# Business_Card.net
KiCad netlist of a schematic drawn in EAGLE
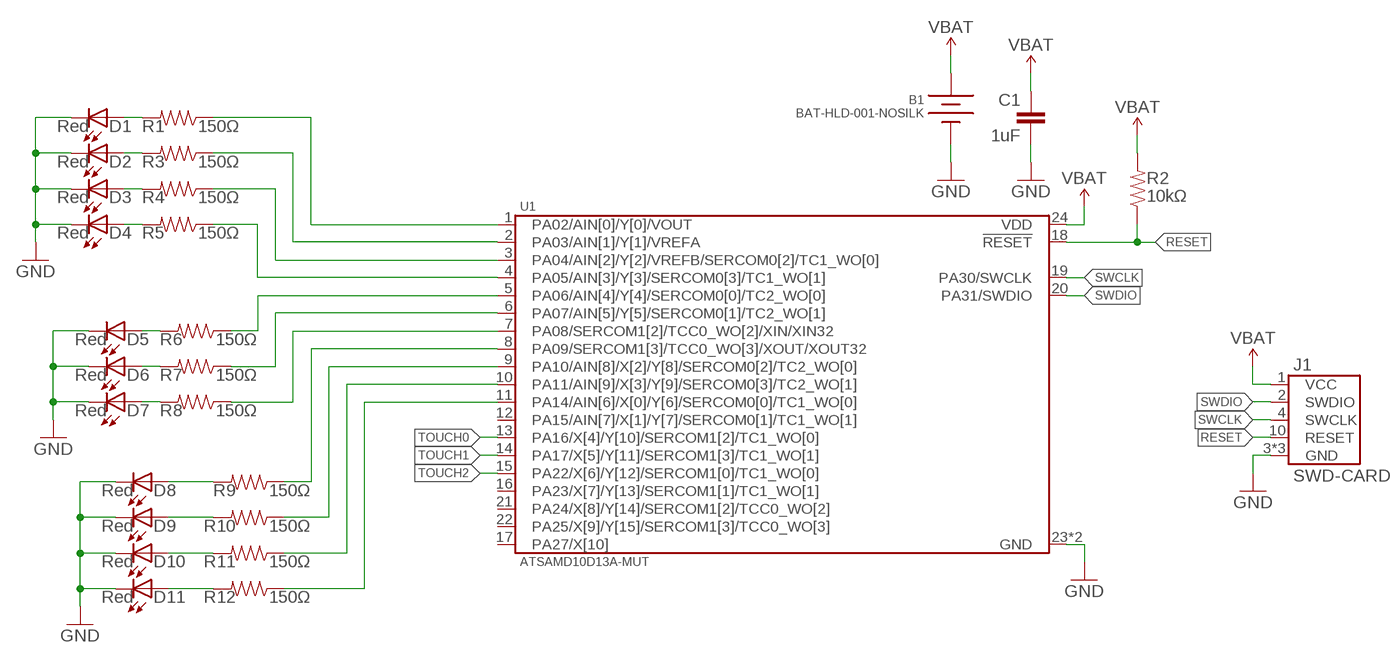
[diagram p0: schematic, sheet 1]

(export (version "E")
  (design (tool "Eeschema 10.0.6"))
  (components
    (comp (ref "B1")
      (value "BAT-HLD-001-NOSILK")
      (footprint "eagle-import:BK-912-G-TR")
      (libsource (lib "eagle-import") (part "BAT-HLD-001-NOSILK"))
    )
    (comp (ref "C1")
      (value "1uF")
      (footprint "eagle-import:0603-CAP")
      (libsource (lib "eagle-import") (part "CAP-0603"))
    )
    (comp (ref "D1")
      (value "Red")
      (footprint "eagle-import:0805-LED")
      (libsource (lib "eagle-import") (part "LED-0805"))
    )
    (comp (ref "D2")
      (value "Red")
      (footprint "eagle-import:0805-LED")
      (libsource (lib "eagle-import") (part "LED-0805"))
    )
    (comp (ref "D3")
      (value "Red")
      (footprint "eagle-import:0805-LED")
      (libsource (lib "eagle-import") (part "LED-0805"))
    )
    (comp (ref "D4")
      (value "Red")
      (footprint "eagle-import:0805-LED")
      (libsource (lib "eagle-import") (part "LED-0805"))
    )
    (comp (ref "D5")
      (value "Red")
      (footprint "eagle-import:0805-LED")
      (libsource (lib "eagle-import") (part "LED-0805"))
    )
    (comp (ref "D6")
      (value "Red")
      (footprint "eagle-import:0805-LED")
      (libsource (lib "eagle-import") (part "LED-0805"))
    )
    (comp (ref "D7")
      (value "Red")
      (footprint "eagle-import:0805-LED")
      (libsource (lib "eagle-import") (part "LED-0805"))
    )
    (comp (ref "D8")
      (value "Red")
      (footprint "eagle-import:0805-LED")
      (libsource (lib "eagle-import") (part "LED-0805"))
    )
    (comp (ref "D9")
      (value "Red")
      (footprint "eagle-import:0805-LED")
      (libsource (lib "eagle-import") (part "LED-0805"))
    )
    (comp (ref "D10")
      (value "Red")
      (footprint "eagle-import:0805-LED")
      (libsource (lib "eagle-import") (part "LED-0805"))
    )
    (comp (ref "D11")
      (value "Red")
      (footprint "eagle-import:0805-LED")
      (libsource (lib "eagle-import") (part "LED-0805"))
    )
    (comp (ref "J1")
      (value "SWD-CARD")
      (footprint "eagle-import:CWR-170-10-0203")
      (libsource (lib "eagle-import") (part "SWD-CARD"))
    )
    (comp (ref "R1")
      (value "150Ω")
      (footprint "eagle-import:0603-CAP")
      (libsource (lib "eagle-import") (part "RESISTOR-0603"))
    )
    (comp (ref "R2")
      (value "10kΩ")
      (footprint "eagle-import:0603-CAP")
      (libsource (lib "eagle-import") (part "RESISTOR-0603"))
    )
    (comp (ref "R3")
      (value "150Ω")
      (footprint "eagle-import:0603-CAP")
      (libsource (lib "eagle-import") (part "RESISTOR-0603"))
    )
    (comp (ref "R4")
      (value "150Ω")
      (footprint "eagle-import:0603-CAP")
      (libsource (lib "eagle-import") (part "RESISTOR-0603"))
    )
    (comp (ref "R5")
      (value "150Ω")
      (footprint "eagle-import:0603-CAP")
      (libsource (lib "eagle-import") (part "RESISTOR-0603"))
    )
    (comp (ref "R6")
      (value "150Ω")
      (footprint "eagle-import:0603-CAP")
      (libsource (lib "eagle-import") (part "RESISTOR-0603"))
    )
    (comp (ref "R7")
      (value "150Ω")
      (footprint "eagle-import:0603-CAP")
      (libsource (lib "eagle-import") (part "RESISTOR-0603"))
    )
    (comp (ref "R8")
      (value "150Ω")
      (footprint "eagle-import:0603-CAP")
      (libsource (lib "eagle-import") (part "RESISTOR-0603"))
    )
    (comp (ref "R9")
      (value "150Ω")
      (footprint "eagle-import:0603-CAP")
      (libsource (lib "eagle-import") (part "RESISTOR-0603"))
    )
    (comp (ref "R10")
      (value "150Ω")
      (footprint "eagle-import:0603-CAP")
      (libsource (lib "eagle-import") (part "RESISTOR-0603"))
    )
    (comp (ref "R11")
      (value "150Ω")
      (footprint "eagle-import:0603-CAP")
      (libsource (lib "eagle-import") (part "RESISTOR-0603"))
    )
    (comp (ref "R12")
      (value "150Ω")
      (footprint "eagle-import:0603-CAP")
      (libsource (lib "eagle-import") (part "RESISTOR-0603"))
    )
    (comp (ref "U1")
      (value "ATSAMD10D13A-MUT")
      (footprint "eagle-import:QFN-24")
      (libsource (lib "eagle-import") (part "ATSAMD10D13A-MUT"))
    )
  )
  (nets
    (net (code "1") (name "GND") (class "Default")
      (node (ref "B1") (pin "-") (pinfunction "N_-") (pintype "bidirectional"))
      (node (ref "C1") (pin "2") (pinfunction "2_2") (pintype "passive"))
      (node (ref "D1") (pin "C") (pinfunction "C_C") (pintype "passive"))
      (node (ref "D10") (pin "C") (pinfunction "C_C") (pintype "passive"))
      (node (ref "D11") (pin "C") (pinfunction "C_C") (pintype "passive"))
      (node (ref "D2") (pin "C") (pinfunction "C_C") (pintype "passive"))
      (node (ref "D3") (pin "C") (pinfunction "C_C") (pintype "passive"))
      (node (ref "D4") (pin "C") (pinfunction "C_C") (pintype "passive"))
      (node (ref "D5") (pin "C") (pinfunction "C_C") (pintype "passive"))
      (node (ref "D6") (pin "C") (pinfunction "C_C") (pintype "passive"))
      (node (ref "D7") (pin "C") (pinfunction "C_C") (pintype "passive"))
      (node (ref "D8") (pin "C") (pinfunction "C_C") (pintype "passive"))
      (node (ref "D9") (pin "C") (pinfunction "C_C") (pintype "passive"))
      (node (ref "J1") (pin "3") (pinfunction "GND_3") (pintype "bidirectional"))
      (node (ref "J1") (pin "5") (pinfunction "GND_5") (pintype "bidirectional"))
      (node (ref "J1") (pin "9") (pinfunction "GND_9") (pintype "bidirectional"))
      (node (ref "U1") (pin "23") (pinfunction "GND_23") (pintype "bidirectional"))
      (node (ref "U1") (pin "P$1") (pinfunction "GND_P$1") (pintype "bidirectional"))
    )
    (net (code "2") (name "Net-(D1-PadA)") (class "Default")
      (node (ref "D1") (pin "A") (pinfunction "A_A") (pintype "passive"))
      (node (ref "R1") (pin "2") (pinfunction "2_2") (pintype "passive"))
    )
    (net (code "3") (name "Net-(D2-PadA)") (class "Default")
      (node (ref "D2") (pin "A") (pinfunction "A_A") (pintype "passive"))
      (node (ref "R3") (pin "2") (pinfunction "2_2") (pintype "passive"))
    )
    (net (code "4") (name "Net-(D3-PadA)") (class "Default")
      (node (ref "D3") (pin "A") (pinfunction "A_A") (pintype "passive"))
      (node (ref "R4") (pin "2") (pinfunction "2_2") (pintype "passive"))
    )
    (net (code "5") (name "Net-(D4-PadA)") (class "Default")
      (node (ref "D4") (pin "A") (pinfunction "A_A") (pintype "passive"))
      (node (ref "R5") (pin "2") (pinfunction "2_2") (pintype "passive"))
    )
    (net (code "6") (name "Net-(D5-PadA)") (class "Default")
      (node (ref "D5") (pin "A") (pinfunction "A_A") (pintype "passive"))
      (node (ref "R6") (pin "2") (pinfunction "2_2") (pintype "passive"))
    )
    (net (code "7") (name "Net-(D6-PadA)") (class "Default")
      (node (ref "D6") (pin "A") (pinfunction "A_A") (pintype "passive"))
      (node (ref "R7") (pin "2") (pinfunction "2_2") (pintype "passive"))
    )
    (net (code "8") (name "Net-(D7-PadA)") (class "Default")
      (node (ref "D7") (pin "A") (pinfunction "A_A") (pintype "passive"))
      (node (ref "R8") (pin "2") (pinfunction "2_2") (pintype "passive"))
    )
    (net (code "9") (name "Net-(D8-PadA)") (class "Default")
      (node (ref "D8") (pin "A") (pinfunction "A_A") (pintype "passive"))
      (node (ref "R9") (pin "2") (pinfunction "2_2") (pintype "passive"))
    )
    (net (code "10") (name "Net-(D9-PadA)") (class "Default")
      (node (ref "D9") (pin "A") (pinfunction "A_A") (pintype "passive"))
      (node (ref "R10") (pin "2") (pinfunction "2_2") (pintype "passive"))
    )
    (net (code "11") (name "Net-(D10-PadA)") (class "Default")
      (node (ref "D10") (pin "A") (pinfunction "A_A") (pintype "passive"))
      (node (ref "R11") (pin "2") (pinfunction "2_2") (pintype "passive"))
    )
    (net (code "12") (name "Net-(D11-PadA)") (class "Default")
      (node (ref "D11") (pin "A") (pinfunction "A_A") (pintype "passive"))
      (node (ref "R12") (pin "2") (pinfunction "2_2") (pintype "passive"))
    )
    (net (code "13") (name "Net-(U1-PA02{slash}AIN[0]{slash}Y[0]{slash}VOUT)") (class "Default")
      (node (ref "R1") (pin "1") (pinfunction "1_1") (pintype "passive"))
      (node (ref "U1") (pin "1") (pinfunction "PA02/AIN[0]/Y[0]/VOUT_1") (pintype "bidirectional"))
    )
    (net (code "14") (name "Net-(U1-PA03{slash}AIN[1]{slash}Y[1]{slash}VREFA)") (class "Default")
      (node (ref "R3") (pin "1") (pinfunction "1_1") (pintype "passive"))
      (node (ref "U1") (pin "2") (pinfunction "PA03/AIN[1]/Y[1]/VREFA_2") (pintype "bidirectional"))
    )
    (net (code "15") (name "Net-(U1-PA04{slash}AIN[2]{slash}Y[2]{slash}VREFB{slash}SERCOM0[2]{slash}TC1_WO[0])") (class "Default")
      (node (ref "R4") (pin "1") (pinfunction "1_1") (pintype "passive"))
      (node (ref "U1") (pin "3") (pinfunction "PA04/AIN[2]/Y[2]/VREFB/SERCOM0[2]/TC1_WO[0]_3") (pintype "bidirectional"))
    )
    (net (code "16") (name "Net-(U1-PA05{slash}AIN[3]{slash}Y[3]{slash}SERCOM0[3]{slash}TC1_WO[1])") (class "Default")
      (node (ref "R5") (pin "1") (pinfunction "1_1") (pintype "passive"))
      (node (ref "U1") (pin "4") (pinfunction "PA05/AIN[3]/Y[3]/SERCOM0[3]/TC1_WO[1]_4") (pintype "bidirectional"))
    )
    (net (code "17") (name "Net-(U1-PA06{slash}AIN[4]{slash}Y[4]{slash}SERCOM0[0]{slash}TC2_WO[0])") (class "Default")
      (node (ref "R6") (pin "1") (pinfunction "1_1") (pintype "passive"))
      (node (ref "U1") (pin "5") (pinfunction "PA06/AIN[4]/Y[4]/SERCOM0[0]/TC2_WO[0]_5") (pintype "bidirectional"))
    )
    (net (code "18") (name "Net-(U1-PA07{slash}AIN[5]{slash}Y[5]{slash}SERCOM0[1]{slash}TC2_WO[1])") (class "Default")
      (node (ref "R7") (pin "1") (pinfunction "1_1") (pintype "passive"))
      (node (ref "U1") (pin "6") (pinfunction "PA07/AIN[5]/Y[5]/SERCOM0[1]/TC2_WO[1]_6") (pintype "bidirectional"))
    )
    (net (code "19") (name "Net-(U1-PA08{slash}SERCOM1[2]{slash}TCC0_WO[2]{slash}XIN{slash}XIN32)") (class "Default")
      (node (ref "R8") (pin "1") (pinfunction "1_1") (pintype "passive"))
      (node (ref "U1") (pin "7") (pinfunction "PA08/SERCOM1[2]/TCC0_WO[2]/XIN/XIN32_7") (pintype "bidirectional"))
    )
    (net (code "20") (name "Net-(U1-PA09{slash}SERCOM1[3]{slash}TCC0_WO[3]{slash}XOUT{slash}XOUT32)") (class "Default")
      (node (ref "R9") (pin "1") (pinfunction "1_1") (pintype "passive"))
      (node (ref "U1") (pin "8") (pinfunction "PA09/SERCOM1[3]/TCC0_WO[3]/XOUT/XOUT32_8") (pintype "bidirectional"))
    )
    (net (code "21") (name "Net-(U1-PA10{slash}AIN[8]{slash}X[2]{slash}Y[8]{slash}SERCOM0[2]{slash}TC2_WO[0])") (class "Default")
      (node (ref "R10") (pin "1") (pinfunction "1_1") (pintype "passive"))
      (node (ref "U1") (pin "9") (pinfunction "PA10/AIN[8]/X[2]/Y[8]/SERCOM0[2]/TC2_WO[0]_9") (pintype "bidirectional"))
    )
    (net (code "22") (name "Net-(U1-PA11{slash}AIN[9]{slash}X[3]{slash}Y[9]{slash}SERCOM0[3]{slash}TC2_WO[1])") (class "Default")
      (node (ref "R11") (pin "1") (pinfunction "1_1") (pintype "passive"))
      (node (ref "U1") (pin "10") (pinfunction "PA11/AIN[9]/X[3]/Y[9]/SERCOM0[3]/TC2_WO[1]_10") (pintype "bidirectional"))
    )
    (net (code "23") (name "Net-(U1-PA14{slash}AIN[6]{slash}X[0]{slash}Y[6]{slash}SERCOM0[0]{slash}TC1_WO[0])") (class "Default")
      (node (ref "R12") (pin "1") (pinfunction "1_1") (pintype "passive"))
      (node (ref "U1") (pin "11") (pinfunction "PA14/AIN[6]/X[0]/Y[6]/SERCOM0[0]/TC1_WO[0]_11") (pintype "bidirectional"))
    )
    (net (code "24") (name "RESET") (class "Default")
      (node (ref "J1") (pin "10") (pinfunction "RESET_10") (pintype "bidirectional"))
      (node (ref "R2") (pin "1") (pinfunction "1_1") (pintype "passive"))
      (node (ref "U1") (pin "18") (pinfunction "~{RESET}_18") (pintype "bidirectional"))
    )
    (net (code "25") (name "SWCLK") (class "Default")
      (node (ref "J1") (pin "4") (pinfunction "SWCLK_4") (pintype "bidirectional"))
      (node (ref "U1") (pin "19") (pinfunction "PA30/SWCLK_19") (pintype "bidirectional"))
    )
    (net (code "26") (name "SWDIO") (class "Default")
      (node (ref "J1") (pin "2") (pinfunction "SWDIO_2") (pintype "bidirectional"))
      (node (ref "U1") (pin "20") (pinfunction "PA31/SWDIO_20") (pintype "bidirectional"))
    )
    (net (code "27") (name "TOUCH0") (class "Default")
      (node (ref "U1") (pin "13") (pinfunction "PA16/X[4]/Y[10]/SERCOM1[2]/TC1_WO[0]_13") (pintype "bidirectional"))
    )
    (net (code "28") (name "TOUCH1") (class "Default")
      (node (ref "U1") (pin "14") (pinfunction "PA17/X[5]/Y[11]/SERCOM1[3]/TC1_WO[1]_14") (pintype "bidirectional"))
    )
    (net (code "29") (name "TOUCH2") (class "Default")
      (node (ref "U1") (pin "15") (pinfunction "PA22/X[6]/Y[12]/SERCOM1[0]/TC1_WO[0]_15") (pintype "bidirectional"))
    )
    (net (code "30") (name "VBAT") (class "Default")
      (node (ref "B1") (pin "+1") (pinfunction "P_+1") (pintype "bidirectional"))
      (node (ref "B1") (pin "+2") (pinfunction "P_+2") (pintype "bidirectional"))
      (node (ref "C1") (pin "1") (pinfunction "1_1") (pintype "passive"))
      (node (ref "J1") (pin "1") (pinfunction "VCC_1") (pintype "bidirectional"))
      (node (ref "R2") (pin "2") (pinfunction "2_2") (pintype "passive"))
      (node (ref "U1") (pin "24") (pinfunction "VDD_24") (pintype "bidirectional"))
    )
    (net (code "31") (name "unconnected-(U1-PA15{slash}AIN[7]{slash}X[1]{slash}Y[7]{slash}SERCOM0[1]{slash}TC1_WO[1]-Pad12)") (class "Default")
      (node (ref "U1") (pin "12") (pinfunction "PA15/AIN[7]/X[1]/Y[7]/SERCOM0[1]/TC1_WO[1]_12") (pintype "bidirectional"))
    )
    (net (code "32") (name "unconnected-(U1-PA23{slash}X[7]{slash}Y[13]{slash}SERCOM1[1]{slash}TC1_WO[1]-Pad16)") (class "Default")
      (node (ref "U1") (pin "16") (pinfunction "PA23/X[7]/Y[13]/SERCOM1[1]/TC1_WO[1]_16") (pintype "bidirectional"))
    )
    (net (code "33") (name "unconnected-(U1-PA24{slash}X[8]{slash}Y[14]{slash}SERCOM1[2]{slash}TCC0_WO[2]-Pad21)") (class "Default")
      (node (ref "U1") (pin "21") (pinfunction "PA24/X[8]/Y[14]/SERCOM1[2]/TCC0_WO[2]_21") (pintype "bidirectional"))
    )
    (net (code "34") (name "unconnected-(U1-PA25{slash}X[9]{slash}Y[15]{slash}SERCOM1[3]{slash}TCC0_WO[3]-Pad22)") (class "Default")
      (node (ref "U1") (pin "22") (pinfunction "PA25/X[9]/Y[15]/SERCOM1[3]/TCC0_WO[3]_22") (pintype "bidirectional"))
    )
    (net (code "35") (name "unconnected-(U1-PA27{slash}X[10]-Pad17)") (class "Default")
      (node (ref "U1") (pin "17") (pinfunction "PA27/X[10]_17") (pintype "bidirectional"))
    )
  )
)
